# Timer.net
KiCad netlist of a schematic drawn in EAGLE
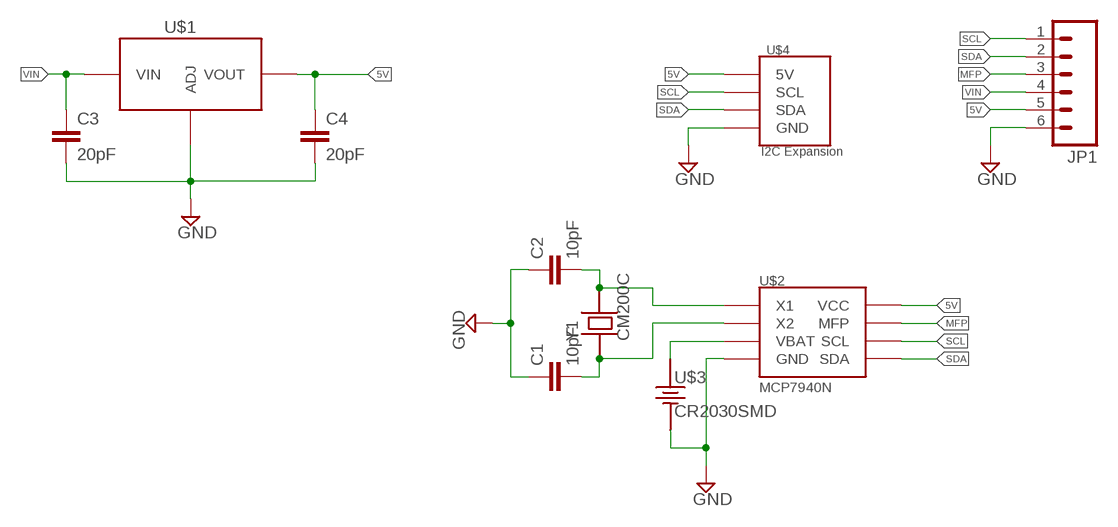
[diagram p0: schematic, sheet 1]

(export (version "E")
  (design (tool "Eeschema 10.0.6"))
  (components
    (comp (ref "C1")
      (value "10pF")
      (footprint "eagle-import:0603-CAP")
      (libsource (lib "eagle-import") (part "CAP0603-CAP"))
    )
    (comp (ref "C2")
      (value "10pF")
      (footprint "eagle-import:0603-CAP")
      (libsource (lib "eagle-import") (part "CAP0603-CAP"))
    )
    (comp (ref "C3")
      (value "20pF")
      (footprint "eagle-import:0603-CAP")
      (libsource (lib "eagle-import") (part "CAP0603-CAP"))
    )
    (comp (ref "C4")
      (value "20pF")
      (footprint "eagle-import:0603-CAP")
      (libsource (lib "eagle-import") (part "CAP0603-CAP"))
    )
    (comp (ref "JP1")
      (value "M06SILK_FEMALE_PTH")
      (footprint "eagle-import:1X06")
      (libsource (lib "eagle-import") (part "M06SILK_FEMALE_PTH"))
    )
    (comp (ref "U$1")
      (value "LM1117")
      (footprint "eagle-import:SOT223")
      (libsource (lib "eagle-import") (part "LM1117"))
    )
    (comp (ref "U$2")
      (value "MCP7940NSOIC-8")
      (footprint "eagle-import:SOIC-8")
      (libsource (lib "eagle-import") (part "MCP7940NSOIC-8"))
    )
    (comp (ref "U$3")
      (value "CR2030SMD")
      (footprint "eagle-import:CR2030SMD")
      (libsource (lib "eagle-import") (part "CR2030SMD"))
    )
    (comp (ref "U$4")
      (value "I2CEXPANSION")
      (footprint "eagle-import:JST-4-PTH-VERT")
      (libsource (lib "eagle-import") (part "I2CEXPANSION"))
    )
    (comp (ref "Y1")
      (value "CM200C")
      (footprint "eagle-import:CM2##")
      (libsource (lib "eagle-import") (part "CM200C"))
    )
  )
  (nets
    (net (code "1") (name "5V") (class "Default")
      (node (ref "C4") (pin "1") (pinfunction "1_1") (pintype "passive"))
      (node (ref "JP1") (pin "5") (pinfunction "5_5") (pintype "passive"))
      (node (ref "U$1") (pin "P2") (pinfunction "VOUT_P2") (pintype "bidirectional"))
      (node (ref "U$1") (pin "P4") (pinfunction "VOUT_P4") (pintype "bidirectional"))
      (node (ref "U$2") (pin "VCC") (pinfunction "VCC_VCC") (pintype "bidirectional"))
      (node (ref "U$4") (pin "1") (pinfunction "5V_1") (pintype "bidirectional"))
    )
    (net (code "2") (name "GND") (class "Default")
      (node (ref "C1") (pin "1") (pinfunction "1_1") (pintype "passive"))
      (node (ref "C2") (pin "1") (pinfunction "1_1") (pintype "passive"))
      (node (ref "C3") (pin "2") (pinfunction "2_2") (pintype "passive"))
      (node (ref "C4") (pin "2") (pinfunction "2_2") (pintype "passive"))
      (node (ref "JP1") (pin "6") (pinfunction "6_6") (pintype "passive"))
      (node (ref "U$1") (pin "P1") (pinfunction "ADJ_P1") (pintype "bidirectional"))
      (node (ref "U$2") (pin "GND") (pinfunction "GND_GND") (pintype "bidirectional"))
      (node (ref "U$3") (pin "GND") (pinfunction "NEG_GND") (pintype "bidirectional"))
      (node (ref "U$3") (pin "GND1") (pinfunction "NEG_GND1") (pintype "bidirectional"))
      (node (ref "U$4") (pin "4") (pinfunction "GND_4") (pintype "bidirectional"))
    )
    (net (code "3") (name "MFP") (class "Default")
      (node (ref "JP1") (pin "3") (pinfunction "3_3") (pintype "passive"))
      (node (ref "U$2") (pin "MFP") (pinfunction "MFP_MFP") (pintype "bidirectional"))
    )
    (net (code "4") (name "Net-(U$2-PadVBAT)") (class "Default")
      (node (ref "U$2") (pin "VBAT") (pinfunction "VBAT_VBAT") (pintype "bidirectional"))
      (node (ref "U$3") (pin "POS") (pinfunction "POS_POS") (pintype "bidirectional"))
    )
    (net (code "5") (name "Net-(Y1-P$1)") (class "Default")
      (node (ref "C1") (pin "2") (pinfunction "2_2") (pintype "passive"))
      (node (ref "U$2") (pin "X2") (pinfunction "X2_X2") (pintype "bidirectional"))
      (node (ref "Y1") (pin "1") (pinfunction "P$1_1") (pintype "bidirectional"))
    )
    (net (code "6") (name "Net-(Y1-P$2)") (class "Default")
      (node (ref "C2") (pin "2") (pinfunction "2_2") (pintype "passive"))
      (node (ref "U$2") (pin "X1") (pinfunction "X1_X1") (pintype "bidirectional"))
      (node (ref "Y1") (pin "4") (pinfunction "P$2_4") (pintype "bidirectional"))
    )
    (net (code "7") (name "SCL") (class "Default")
      (node (ref "JP1") (pin "1") (pinfunction "1_1") (pintype "passive"))
      (node (ref "U$2") (pin "SCL") (pinfunction "SCL_SCL") (pintype "bidirectional"))
      (node (ref "U$4") (pin "2") (pinfunction "SCL_2") (pintype "bidirectional"))
    )
    (net (code "8") (name "SDA") (class "Default")
      (node (ref "JP1") (pin "2") (pinfunction "2_2") (pintype "passive"))
      (node (ref "U$2") (pin "SDA") (pinfunction "SDA_SDA") (pintype "bidirectional"))
      (node (ref "U$4") (pin "3") (pinfunction "SDA_3") (pintype "bidirectional"))
    )
    (net (code "9") (name "VIN") (class "Default")
      (node (ref "C3") (pin "1") (pinfunction "1_1") (pintype "passive"))
      (node (ref "JP1") (pin "4") (pinfunction "4_4") (pintype "passive"))
      (node (ref "U$1") (pin "P3") (pinfunction "VIN_P3") (pintype "bidirectional"))
    )
  )
)
